# cpx-module1-F.net
KiCad netlist of a schematic drawn in EAGLE
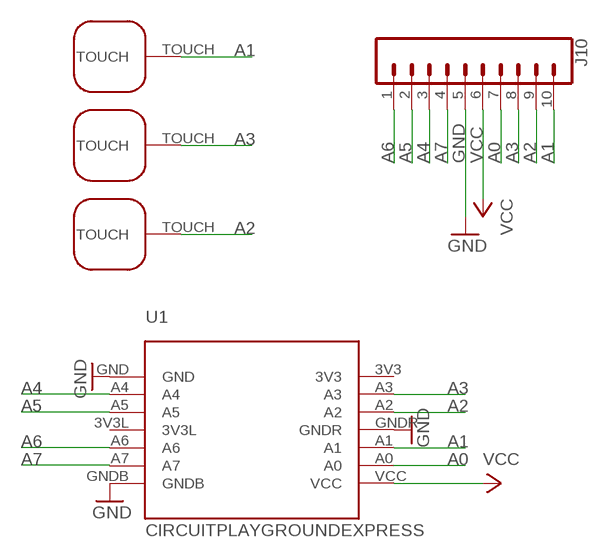
[diagram p0: schematic, sheet 1]

(export (version "E")
  (design (tool "Eeschema 10.0.6"))
  (components
    (comp (ref "J10")
      (value "CONN_10\"")
      (footprint "eagle-import:1X10")
      (libsource (lib "eagle-import") (part "CONN_10{dblquote}"))
    )
    (comp (ref "T1")
      (value "TOUCHPADROUND1")
      (footprint "eagle-import:TOUCHPAD1")
      (libsource (lib "eagle-import") (part "TOUCHPADROUND1"))
    )
    (comp (ref "T2")
      (value "TOUCHPADROUND1")
      (footprint "eagle-import:TOUCHPAD1")
      (libsource (lib "eagle-import") (part "TOUCHPADROUND1"))
    )
    (comp (ref "T4")
      (value "TOUCHPADROUND1")
      (footprint "eagle-import:TOUCHPAD1")
      (libsource (lib "eagle-import") (part "TOUCHPADROUND1"))
    )
    (comp (ref "U1")
      (value "CIRCUITPLAYGROUNDEXPRESS")
      (footprint "eagle-import:CIRCUITPLAYGROUNDEXPRESS")
      (libsource (lib "eagle-import") (part "CIRCUITPLAYGROUNDEXPRESS"))
    )
  )
  (nets
    (net (code "1") (name "/A0") (class "Default")
      (node (ref "J10") (pin "7") (pinfunction "7_7") (pintype "passive"))
      (node (ref "U1") (pin "A0") (pinfunction "A0_A0") (pintype "bidirectional"))
    )
    (net (code "2") (name "/A1") (class "Default")
      (node (ref "J10") (pin "10") (pinfunction "10_10") (pintype "passive"))
      (node (ref "T2") (pin "TOUCH") (pinfunction "TOUCH_TOUCH") (pintype "bidirectional"))
      (node (ref "U1") (pin "A1") (pinfunction "A1_A1") (pintype "bidirectional"))
    )
    (net (code "3") (name "/A2") (class "Default")
      (node (ref "J10") (pin "9") (pinfunction "9_9") (pintype "passive"))
      (node (ref "T4") (pin "TOUCH") (pinfunction "TOUCH_TOUCH") (pintype "bidirectional"))
      (node (ref "U1") (pin "A2") (pinfunction "A2_A2") (pintype "bidirectional"))
    )
    (net (code "4") (name "/A3") (class "Default")
      (node (ref "J10") (pin "8") (pinfunction "8_8") (pintype "passive"))
      (node (ref "T1") (pin "TOUCH") (pinfunction "TOUCH_TOUCH") (pintype "bidirectional"))
      (node (ref "U1") (pin "A3") (pinfunction "A3_A3") (pintype "bidirectional"))
    )
    (net (code "5") (name "/A4") (class "Default")
      (node (ref "J10") (pin "3") (pinfunction "3_3") (pintype "passive"))
      (node (ref "U1") (pin "A4") (pinfunction "A4_A4") (pintype "bidirectional"))
    )
    (net (code "6") (name "/A5") (class "Default")
      (node (ref "J10") (pin "2") (pinfunction "2_2") (pintype "passive"))
      (node (ref "U1") (pin "A5") (pinfunction "A5_A5") (pintype "bidirectional"))
    )
    (net (code "7") (name "/A6") (class "Default")
      (node (ref "J10") (pin "1") (pinfunction "1_1") (pintype "passive"))
      (node (ref "U1") (pin "A6") (pinfunction "A6_A6") (pintype "bidirectional"))
    )
    (net (code "8") (name "/A7") (class "Default")
      (node (ref "J10") (pin "4") (pinfunction "4_4") (pintype "passive"))
      (node (ref "U1") (pin "A7") (pinfunction "A7_A7") (pintype "bidirectional"))
    )
    (net (code "9") (name "GND") (class "Default")
      (node (ref "J10") (pin "5") (pinfunction "5_5") (pintype "passive"))
      (node (ref "U1") (pin "GND") (pinfunction "GND_GND") (pintype "bidirectional"))
      (node (ref "U1") (pin "GNDB") (pinfunction "GNDB_GNDB") (pintype "bidirectional"))
      (node (ref "U1") (pin "GNDR") (pinfunction "GNDR_GNDR") (pintype "bidirectional"))
    )
    (net (code "10") (name "VCC") (class "Default")
      (node (ref "J10") (pin "6") (pinfunction "6_6") (pintype "passive"))
      (node (ref "U1") (pin "VCC") (pinfunction "VCC_VCC") (pintype "bidirectional"))
    )
    (net (code "11") (name "unconnected-(U1-Pad3V3)") (class "Default")
      (node (ref "U1") (pin "3V3") (pinfunction "3V3_3V3") (pintype "bidirectional"))
    )
    (net (code "12") (name "unconnected-(U1-Pad3V3L)") (class "Default")
      (node (ref "U1") (pin "3V3L") (pinfunction "3V3L_3V3L") (pintype "bidirectional"))
    )
  )
)
